# FoxSense_Power.net
KiCad netlist of a schematic drawn in Altium Designer
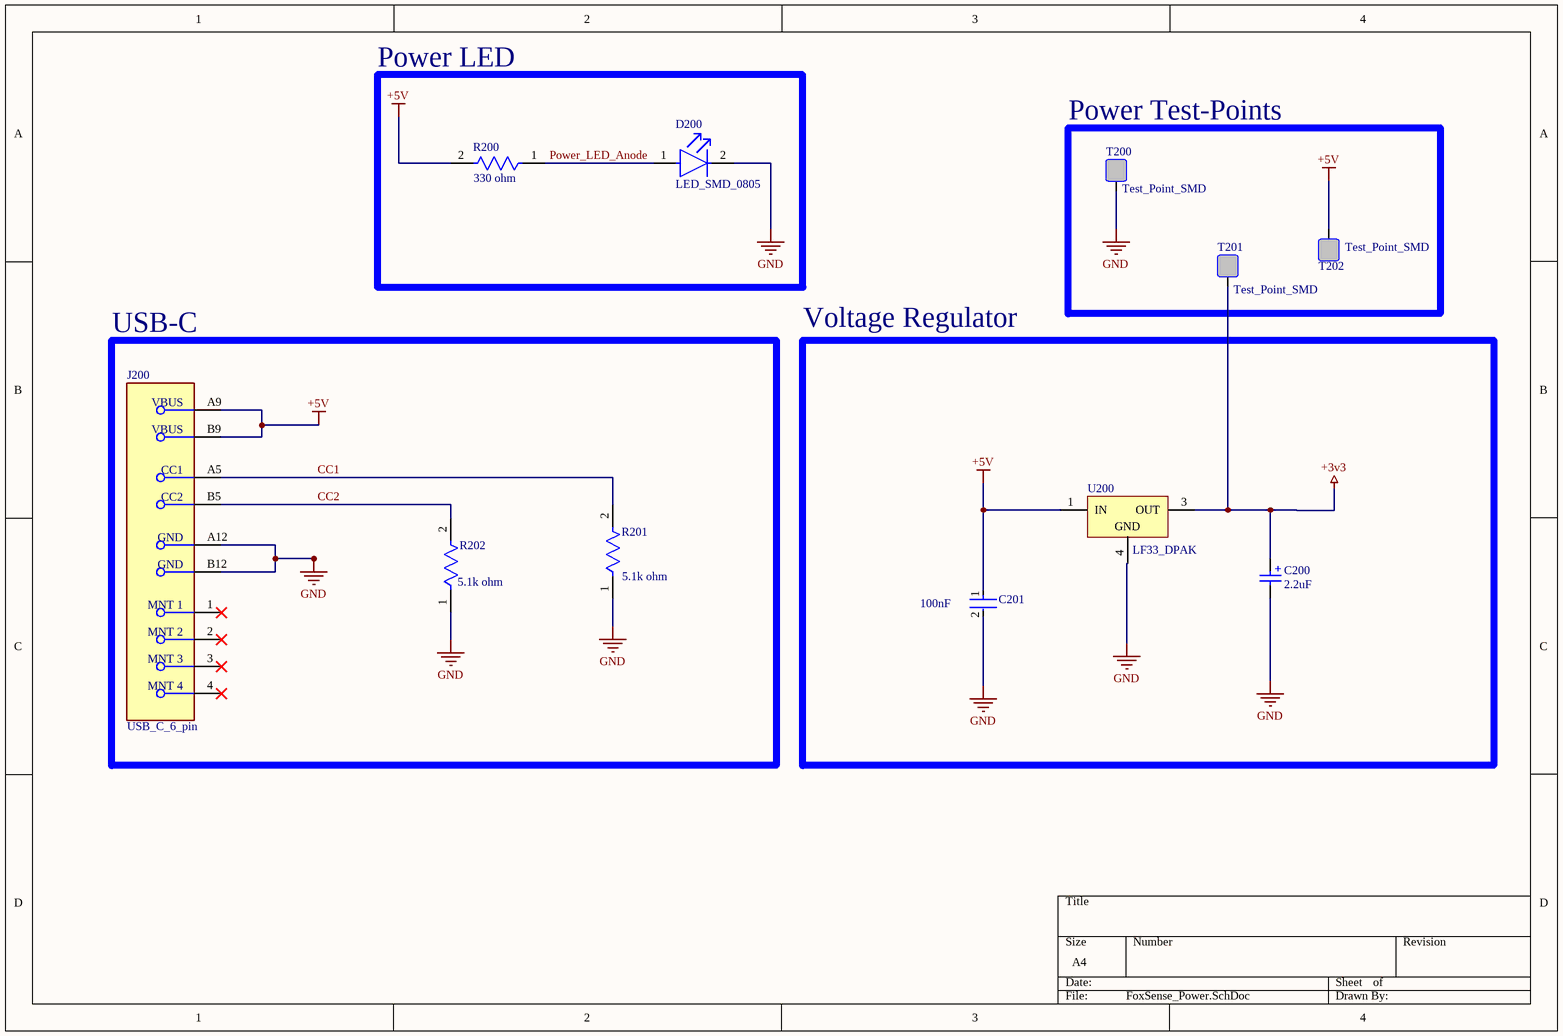
[diagram p0: FoxSense_Power.SchDoc]

(export (version "E")
  (design (tool "Eeschema 10.0.6"))
  (components
    (comp (ref "C200")
      (value "2.2uF")
      (footprint "Capacitor_SMD_Electrolyte_2.2uF")
      (description "Capacitor SMD Electrolyte 2.2uF")
      (libsource (lib "Fox_Schlib") (part "Capacitor_SMD_Electrolyte_2.2uF"))
    )
    (comp (ref "C201")
      (value "100nF")
      (footprint "Capacitor_SMD_0805")
      (description "capacitor smd 0805")
      (libsource (lib "Fox_Schlib") (part "Capacitor_SMD_0805"))
    )
    (comp (ref "D200")
      (value "LED_SMD_0805")
      (footprint "LED_SMD_0805")
      (description "LED SMD 0805")
      (libsource (lib "Fox_Schlib") (part "LED_SMD_0805"))
    )
    (comp (ref "J200")
      (value "USB_C_6_pin")
      (footprint "USB_C_6_pin")
      (description "USB C connector 6 pin")
      (libsource (lib "Fox_Schlib") (part "USB_C"))
    )
    (comp (ref "R200")
      (value "330 ohm")
      (footprint "Resistor_SMD_0805")
      (description "Resistor SMD 0805")
      (libsource (lib "Fox_Schlib") (part "Resistor_SMD_0805"))
    )
    (comp (ref "R201")
      (value "5.1k ohm")
      (footprint "Resistor_SMD_0805")
      (description "Resistor SMD 0805")
      (libsource (lib "Fox_Schlib") (part "Resistor_SMD_0805"))
    )
    (comp (ref "R202")
      (value "5.1k ohm")
      (footprint "Resistor_SMD_0805")
      (description "Resistor SMD 0805")
      (libsource (lib "Fox_Schlib") (part "Resistor_SMD_0805"))
    )
    (comp (ref "T200")
      (value "Test_Point_SMD")
      (footprint "TEST_Point_SMD")
      (description "Test Point SMD")
      (libsource (lib "Fox_Schlib") (part "Test_Point_SMD"))
    )
    (comp (ref "T201")
      (value "Test_Point_SMD")
      (footprint "TEST_Point_SMD")
      (description "Test Point SMD")
      (libsource (lib "Fox_Schlib") (part "Test_Point_SMD"))
    )
    (comp (ref "T202")
      (value "Test_Point_SMD")
      (footprint "TEST_Point_SMD")
      (description "Test Point SMD")
      (libsource (lib "Fox_Schlib") (part "Test_Point_SMD"))
    )
    (comp (ref "U200")
      (value "LF33_DPAK")
      (footprint "LF33")
      (description "LF33 DPAK 3.3 voltage regulator")
      (libsource (lib "Fox_Schlib") (part "LF33"))
    )
  )
  (nets
    (net (code "1") (name "+3v3") (class "Default")
      (node (ref "C200") (pin "1") (pinfunction "P_1") (pintype "passive"))
      (node (ref "T201") (pin "1") (pinfunction "1_1") (pintype "passive"))
      (node (ref "U200") (pin "3") (pinfunction "OUT_3") (pintype "passive"))
    )
    (net (code "2") (name "+5V") (class "Default")
      (node (ref "C201") (pin "1") (pinfunction "1_1") (pintype "passive"))
      (node (ref "J200") (pin "A9") (pinfunction "VBUS_A9") (pintype "passive"))
      (node (ref "J200") (pin "B9") (pinfunction "VBUS_B9") (pintype "passive"))
      (node (ref "R200") (pin "2") (pinfunction "2_2") (pintype "passive"))
      (node (ref "T202") (pin "1") (pinfunction "1_1") (pintype "passive"))
      (node (ref "U200") (pin "1") (pinfunction "IN_1") (pintype "power_in"))
    )
    (net (code "3") (name "/CC1") (class "Default")
      (node (ref "J200") (pin "A5") (pinfunction "CC1_A5") (pintype "passive"))
      (node (ref "R201") (pin "2") (pinfunction "2_2") (pintype "passive"))
    )
    (net (code "4") (name "/CC2") (class "Default")
      (node (ref "J200") (pin "B5") (pinfunction "CC2_B5") (pintype "passive"))
      (node (ref "R202") (pin "2") (pinfunction "2_2") (pintype "passive"))
    )
    (net (code "5") (name "/Power_LED_Anode") (class "Default")
      (node (ref "D200") (pin "1") (pinfunction "A_1") (pintype "passive"))
      (node (ref "R200") (pin "1") (pinfunction "1_1") (pintype "passive"))
    )
    (net (code "6") (name "GND") (class "Default")
      (node (ref "C200") (pin "2") (pinfunction "N_2") (pintype "passive"))
      (node (ref "C201") (pin "2") (pinfunction "2_2") (pintype "passive"))
      (node (ref "D200") (pin "2") (pinfunction "C_2") (pintype "passive"))
      (node (ref "J200") (pin "A12") (pinfunction "GND_A12") (pintype "passive"))
      (node (ref "J200") (pin "B12") (pinfunction "GND_B12") (pintype "passive"))
      (node (ref "R201") (pin "1") (pinfunction "1_1") (pintype "passive"))
      (node (ref "R202") (pin "1") (pinfunction "1_1") (pintype "passive"))
      (node (ref "T200") (pin "1") (pinfunction "1_1") (pintype "passive"))
      (node (ref "U200") (pin "4") (pinfunction "GND_4") (pintype "power_in"))
    )
    (net (code "7") (name "unconnected-(J200-MNT_1-Pad1)") (class "Default")
      (node (ref "J200") (pin "1") (pinfunction "MNT_1_1") (pintype "passive+no_connect"))
    )
    (net (code "8") (name "unconnected-(J200-MNT_2-Pad2)") (class "Default")
      (node (ref "J200") (pin "2") (pinfunction "MNT_2_2") (pintype "passive+no_connect"))
    )
    (net (code "9") (name "unconnected-(J200-MNT_3-Pad3)") (class "Default")
      (node (ref "J200") (pin "3") (pinfunction "MNT_3_3") (pintype "passive+no_connect"))
    )
    (net (code "10") (name "unconnected-(J200-MNT_4-Pad4)") (class "Default")
      (node (ref "J200") (pin "4") (pinfunction "MNT_4_4") (pintype "passive+no_connect"))
    )
  )
)
